# OZ440-SE100-CAR003_sheet11.net
KiCad netlist of a schematic drawn in Altium Designer
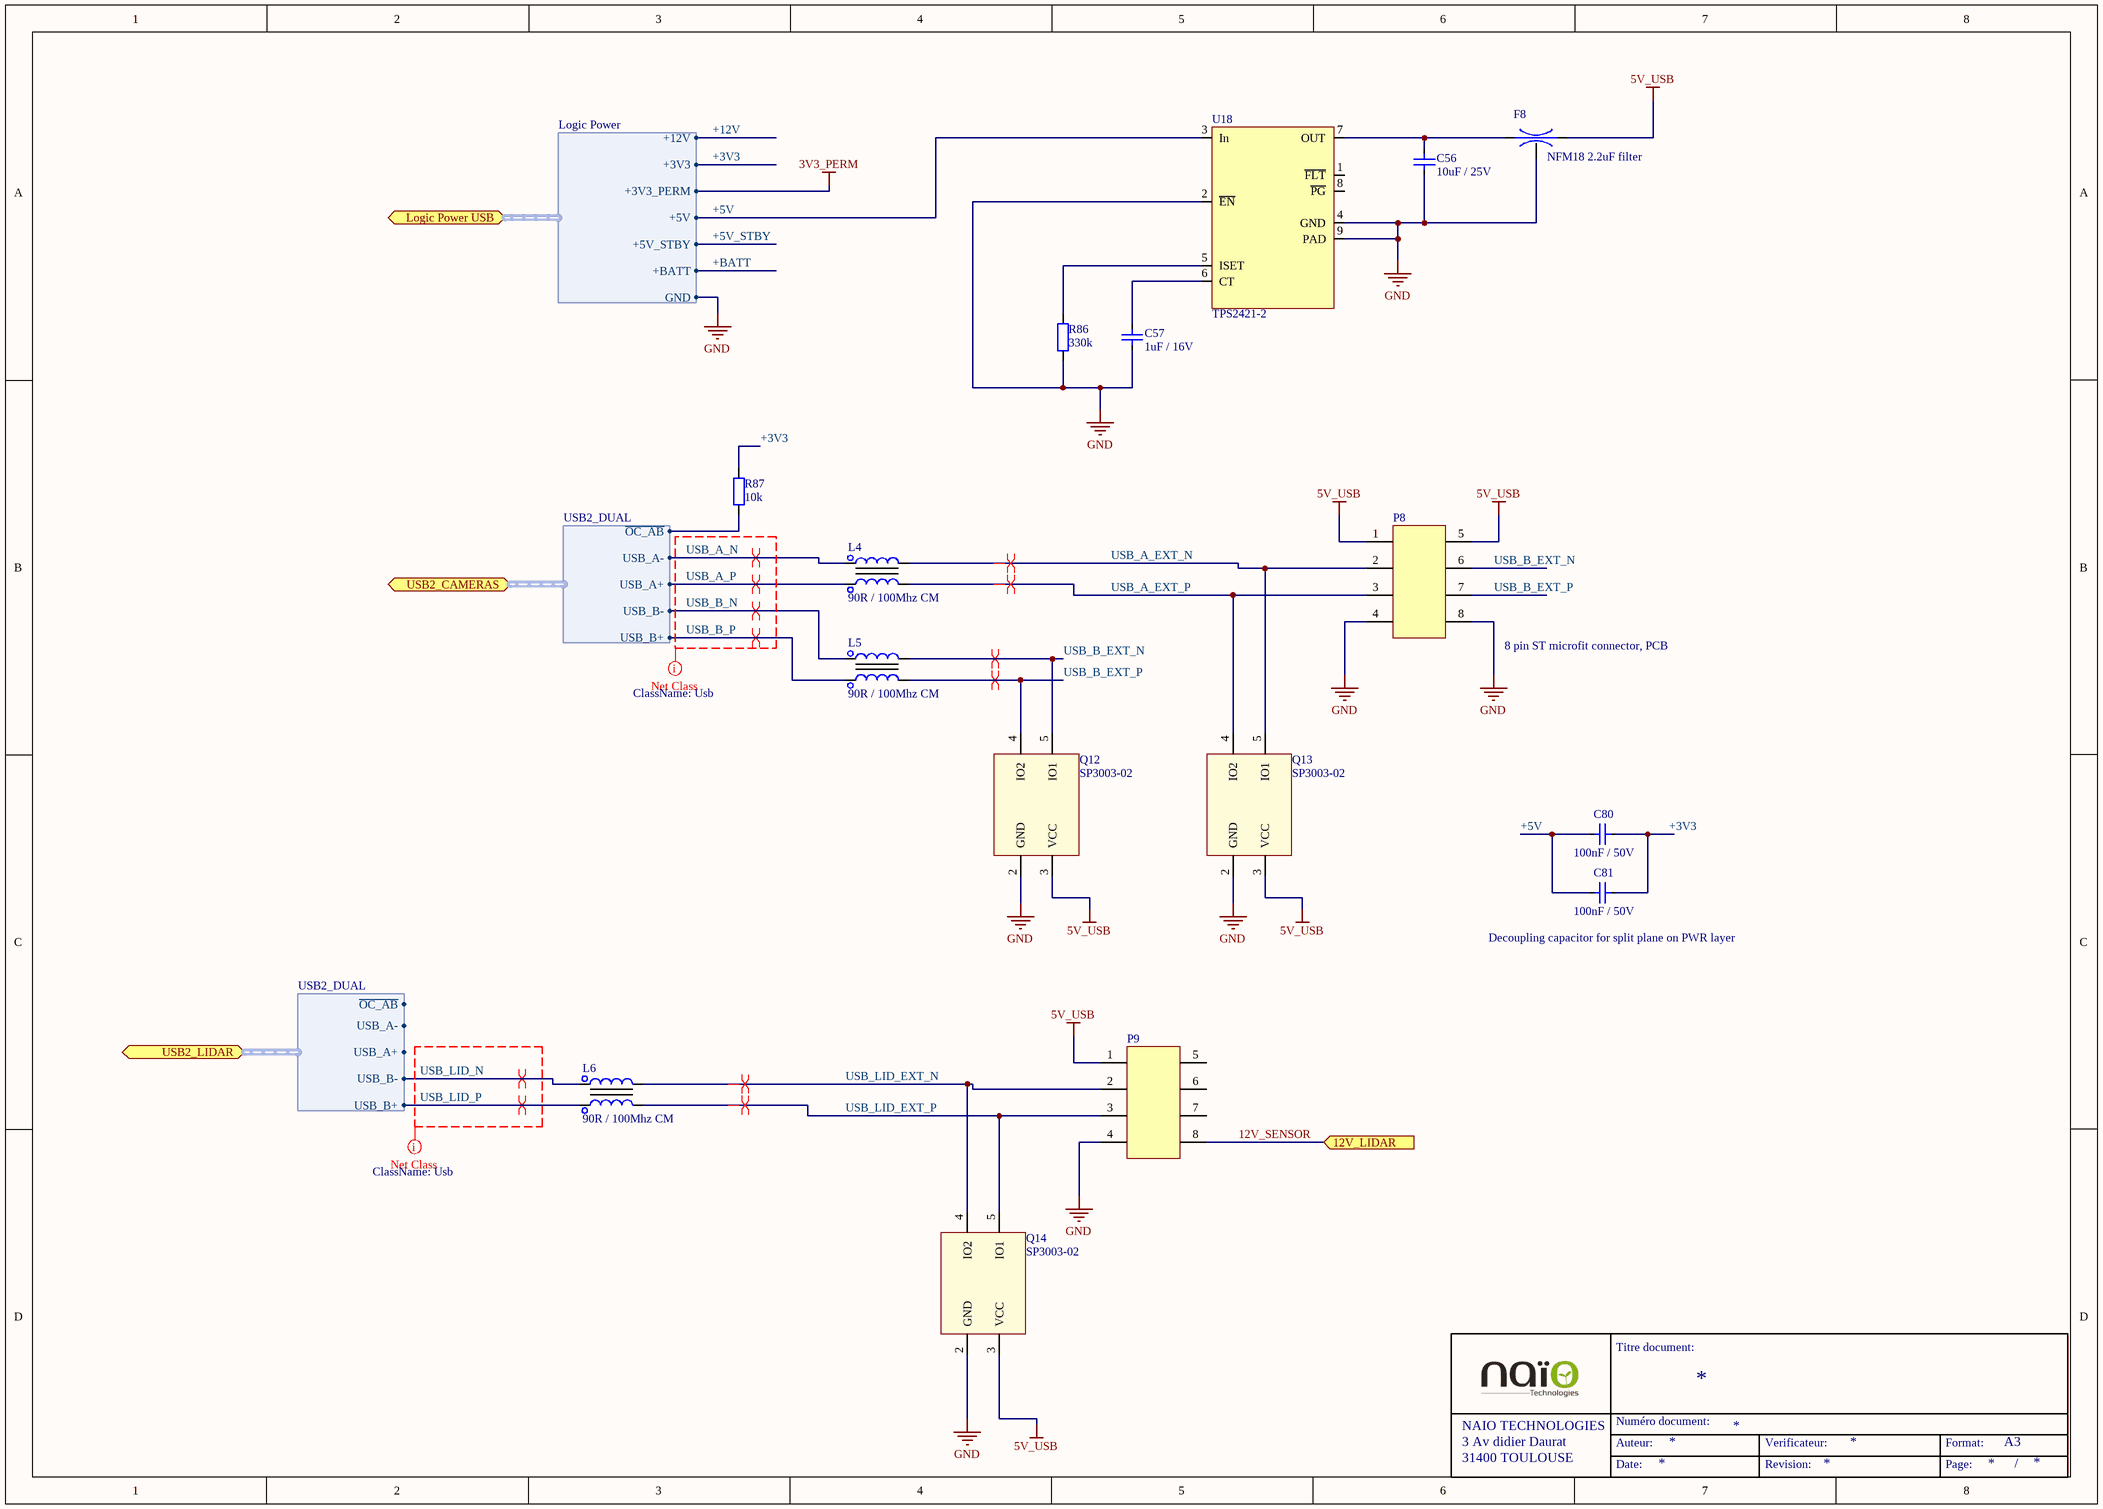
[diagram p0: OZ440-SE100-CAR003_sheet11.SchDoc]

(export (version "E")
  (design (tool "Eeschema 10.0.6"))
  (components
    (comp (ref "C56")
      (value "CAP-SMD")
      (footprint "C1206-STD")
      (description "1206 10uF / 25V X7R ceramic capacitor")
      (fields
        (field (name "DISPLAYED REFERENCE") "10uF / 25V")
        (field (name "TOLERANCE") "+/- 10%")
        (field (name "MANUFACTURER") "Kemet")
      )
      (libsource (lib "lib_NAIO") (part "CAP-SMD"))
    )
    (comp (ref "C57")
      (value "CAP-SMD")
      (footprint "C0805-STD")
      (description "0805 1uF / 16V X7R ceramic capacitor")
      (fields
        (field (name "DISPLAYED REFERENCE") "1uF / 16V")
        (field (name "TOLERANCE") "+/- 10%")
        (field (name "MANUFACTURER") "Kemet")
      )
      (libsource (lib "lib_NAIO") (part "CAP-SMD"))
    )
    (comp (ref "C80")
      (value "CAP-SMD")
      (footprint "C0805-STD")
      (description "0805 100nF / 50V  X7R ceramic capacitor")
      (fields
        (field (name "DISPLAYED REFERENCE") "100nF / 50V")
        (field (name "TOLERANCE") "+/- 10%")
        (field (name "MANUFACTURER") "vishay")
      )
      (libsource (lib "lib_NAIO") (part "CAP-SMD"))
    )
    (comp (ref "C81")
      (value "CAP-SMD")
      (footprint "C0805-STD")
      (description "0805 100nF / 50V  X7R ceramic capacitor")
      (fields
        (field (name "DISPLAYED REFERENCE") "100nF / 50V")
        (field (name "TOLERANCE") "+/- 10%")
        (field (name "MANUFACTURER") "vishay")
      )
      (libsource (lib "lib_NAIO") (part "CAP-SMD"))
    )
    (comp (ref "F8")
      (value "LC_FILTER-STD")
      (footprint "LC_0603-STD")
      (description "2A LC filter")
      (fields
        (field (name "DISPLAYED REFERENCE") "NFM18 2.2uF filter")
        (field (name "MANUFACTURER") "MURATA")
      )
      (libsource (lib "lib_NAIO") (part "LC_FILTER-STD"))
    )
    (comp (ref "L4")
      (value "IND-MC-SMD")
      (footprint "L-SPE-0805_MC_EXC34")
      (description "USB common mode inductor")
      (fields
        (field (name "DISPLAYED REFERENCE") "90R / 100Mhz CM")
        (field (name "MANUFACTURER") "PANASONIC")
      )
      (libsource (lib "lib_NAIO") (part "IND-MC-SMD"))
    )
    (comp (ref "L5")
      (value "IND-MC-SMD")
      (footprint "L-SPE-0805_MC_EXC34")
      (description "USB common mode inductor")
      (fields
        (field (name "DISPLAYED REFERENCE") "90R / 100Mhz CM")
        (field (name "MANUFACTURER") "PANASONIC")
      )
      (libsource (lib "lib_NAIO") (part "IND-MC-SMD"))
    )
    (comp (ref "L6")
      (value "IND-MC-SMD")
      (footprint "L-SPE-0805_MC_EXC34")
      (description "USB common mode inductor")
      (fields
        (field (name "DISPLAYED REFERENCE") "90R / 100Mhz CM")
        (field (name "MANUFACTURER") "PANASONIC")
      )
      (libsource (lib "lib_NAIO") (part "IND-MC-SMD"))
    )
    (comp (ref "P8")
      (value "CONN-SPE-8P_MOLEX_43045-0801")
      (footprint "CONN-SPE_MOLEX_43045-0812")
      (description "8 pin Microfit connector")
      (fields
        (field (name "DISPLAYED REFERENCE") "8 pin ST microfit connector, PCB")
        (field (name "MANUFACTURER") "Molex")
      )
      (libsource (lib "lib_NAIO") (part "CONN-SPE-8P_MOLEX_43045-0801"))
    )
    (comp (ref "P9")
      (value "CONN-SPE-8P_MOLEX_43045-0801")
      (footprint "CONN-SPE_MOLEX_43045-0812")
      (description "8 pin Microfit connector")
      (fields (field (name "MANUFACTURER") "Molex"))
      (libsource (lib "lib_NAIO") (part "CONN-SPE-8P_MOLEX_43045-0801"))
    )
    (comp (ref "Q12")
      (value "SP03003_02-SC70")
      (footprint "SC70-SPE-SP3003")
      (description "Low capacitance ESD TVS")
      (fields (field (name "DISPLAYED REFERENCE") "SP3003-02") (field (name "MANUFACTURER") "LITTLEFUSE"))
      (libsource (lib "lib_NAIO") (part "SP03003_02-SC70"))
    )
    (comp (ref "Q13")
      (value "SP03003_02-SC70")
      (footprint "SC70-SPE-SP3003")
      (description "Low capacitance ESD TVS")
      (fields (field (name "DISPLAYED REFERENCE") "SP3003-02") (field (name "MANUFACTURER") "LITTLEFUSE"))
      (libsource (lib "lib_NAIO") (part "SP03003_02-SC70"))
    )
    (comp (ref "Q14")
      (value "SP03003_02-SC70")
      (footprint "SC70-SPE-SP3003")
      (description "Low capacitance ESD TVS")
      (fields (field (name "DISPLAYED REFERENCE") "SP3003-02") (field (name "MANUFACTURER") "LITTLEFUSE"))
      (libsource (lib "lib_NAIO") (part "SP03003_02-SC70"))
    )
    (comp (ref "R86")
      (value "RES-SMD")
      (footprint "R0805-STD")
      (description "330k Ohm 0805 SMD resistor")
      (fields
        (field (name "DISPLAYED REFERENCE") "330k")
        (field (name "TOLERANCE") "1%")
        (field (name "MANUFACTURER") "Vishay")
      )
      (libsource (lib "") (part "RES-SMD_1"))
    )
    (comp (ref "R87")
      (value "RES-SMD")
      (footprint "R0805-STD")
      (description "10k Ohm 0805 SMD resistor")
      (fields
        (field (name "DISPLAYED REFERENCE") "10k")
        (field (name "TOLERANCE") "1 %")
        (field (name "MANUFACTURER") "Vishay")
      )
      (libsource (lib "lib_NAIO") (part "RES-SMD"))
    )
    (comp (ref "U18")
      (value "TPS2421-SO8")
      (footprint "SO8_THERMAL-STD")
      (description "20V-5A Hot plug controller with integrated FET, auto retry")
      (fields (field (name "DISPLAYED REFERENCE") "TPS2421-2") (field (name "MANUFACTURER") "TI"))
      (libsource (lib "lib_NAIO") (part "TPS2421-SO8"))
    )
  )
  (nets
    (net (code "4") (name "/+3V3") (class "Default")
      (node (ref "C80") (pin "1") (pinfunction "1_1") (pintype "passive"))
      (node (ref "C81") (pin "1") (pinfunction "1_1") (pintype "passive"))
      (node (ref "R87") (pin "1") (pinfunction "1_1") (pintype "passive"))
    )
    (net (code "5") (name "/+5V") (class "Default")
      (node (ref "C80") (pin "2") (pinfunction "2_2") (pintype "passive"))
      (node (ref "C81") (pin "2") (pinfunction "2_2") (pintype "passive"))
      (node (ref "U18") (pin "3") (pinfunction "In_3") (pintype "passive"))
    )
    (net (code "9") (name "/12V_SENSOR") (class "Default")
      (node (ref "P9") (pin "8") (pinfunction "8_8") (pintype "passive"))
    )
    (net (code "10") (name "/USB_A_EXT_N") (class "Default")
      (node (ref "L4") (pin "2") (pinfunction "2_2") (pintype "passive"))
      (node (ref "P8") (pin "2") (pinfunction "2_2") (pintype "passive"))
      (node (ref "Q13") (pin "5") (pinfunction "IO1_5") (pintype "passive"))
    )
    (net (code "11") (name "/USB_A_EXT_P") (class "Default")
      (node (ref "L4") (pin "3") (pinfunction "3_3") (pintype "passive"))
      (node (ref "P8") (pin "3") (pinfunction "3_3") (pintype "passive"))
      (node (ref "Q13") (pin "4") (pinfunction "IO2_4") (pintype "passive"))
    )
    (net (code "12") (name "/USB_A_N") (class "Default")
      (node (ref "L4") (pin "1") (pinfunction "1_1") (pintype "passive"))
    )
    (net (code "13") (name "/USB_A_P") (class "Default")
      (node (ref "L4") (pin "4") (pinfunction "4_4") (pintype "passive"))
    )
    (net (code "14") (name "/USB_B_EXT_N") (class "Default")
      (node (ref "L5") (pin "2") (pinfunction "2_2") (pintype "passive"))
      (node (ref "P8") (pin "6") (pinfunction "6_6") (pintype "passive"))
      (node (ref "Q12") (pin "5") (pinfunction "IO1_5") (pintype "passive"))
    )
    (net (code "15") (name "/USB_B_EXT_P") (class "Default")
      (node (ref "L5") (pin "3") (pinfunction "3_3") (pintype "passive"))
      (node (ref "P8") (pin "7") (pinfunction "7_7") (pintype "passive"))
      (node (ref "Q12") (pin "4") (pinfunction "IO2_4") (pintype "passive"))
    )
    (net (code "16") (name "/USB_B_N") (class "Default")
      (node (ref "L5") (pin "1") (pinfunction "1_1") (pintype "passive"))
    )
    (net (code "17") (name "/USB_B_P") (class "Default")
      (node (ref "L5") (pin "4") (pinfunction "4_4") (pintype "passive"))
    )
    (net (code "18") (name "/USB_LID_EXT_N") (class "Default")
      (node (ref "L6") (pin "2") (pinfunction "2_2") (pintype "passive"))
      (node (ref "P9") (pin "2") (pinfunction "2_2") (pintype "passive"))
      (node (ref "Q14") (pin "4") (pinfunction "IO2_4") (pintype "passive"))
    )
    (net (code "19") (name "/USB_LID_EXT_P") (class "Default")
      (node (ref "L6") (pin "3") (pinfunction "3_3") (pintype "passive"))
      (node (ref "P9") (pin "3") (pinfunction "3_3") (pintype "passive"))
      (node (ref "Q14") (pin "5") (pinfunction "IO1_5") (pintype "passive"))
    )
    (net (code "20") (name "/USB_LID_N") (class "Default")
      (node (ref "L6") (pin "1") (pinfunction "1_1") (pintype "passive"))
    )
    (net (code "21") (name "/USB_LID_P") (class "Default")
      (node (ref "L6") (pin "4") (pinfunction "4_4") (pintype "passive"))
    )
    (net (code "25") (name "5V_USB") (class "Default")
      (node (ref "F8") (pin "2") (pinfunction "B_2") (pintype "passive"))
      (node (ref "P8") (pin "1") (pinfunction "1_1") (pintype "passive"))
      (node (ref "P8") (pin "5") (pinfunction "9_5") (pintype "passive"))
      (node (ref "P9") (pin "1") (pinfunction "1_1") (pintype "passive"))
      (node (ref "Q12") (pin "3") (pinfunction "VCC_3") (pintype "passive"))
      (node (ref "Q13") (pin "3") (pinfunction "VCC_3") (pintype "passive"))
      (node (ref "Q14") (pin "3") (pinfunction "VCC_3") (pintype "passive"))
    )
    (net (code "26") (name "GND") (class "Default")
      (node (ref "C56") (pin "1") (pinfunction "1_1") (pintype "passive"))
      (node (ref "C57") (pin "1") (pinfunction "1_1") (pintype "passive"))
      (node (ref "F8") (pin "3") (pinfunction "G_3") (pintype "passive"))
      (node (ref "P8") (pin "4") (pinfunction "7_4") (pintype "passive"))
      (node (ref "P8") (pin "8") (pinfunction "8_8") (pintype "passive"))
      (node (ref "P9") (pin "4") (pinfunction "7_4") (pintype "passive"))
      (node (ref "Q12") (pin "2") (pinfunction "GND_2") (pintype "passive"))
      (node (ref "Q13") (pin "2") (pinfunction "GND_2") (pintype "passive"))
      (node (ref "Q14") (pin "2") (pinfunction "GND_2") (pintype "passive"))
      (node (ref "R86") (pin "1") (pinfunction "1_1") (pintype "passive"))
      (node (ref "U18") (pin "2") (pinfunction "EN_2") (pintype "passive"))
      (node (ref "U18") (pin "4") (pinfunction "GND_4") (pintype "passive"))
      (node (ref "U18") (pin "9") (pinfunction "PAD_9") (pintype "passive"))
    )
    (net (code "27") (name "Net-(F8-A)") (class "Default")
      (node (ref "C56") (pin "2") (pinfunction "2_2") (pintype "passive"))
      (node (ref "F8") (pin "1") (pinfunction "A_1") (pintype "passive"))
      (node (ref "U18") (pin "7") (pinfunction "OUT_7") (pintype "passive"))
    )
    (net (code "28") (name "Net-(U18-CT)") (class "Default")
      (node (ref "C57") (pin "2") (pinfunction "2_2") (pintype "passive"))
      (node (ref "U18") (pin "6") (pinfunction "CT_6") (pintype "passive"))
    )
    (net (code "29") (name "Net-(U18-ISET)") (class "Default")
      (node (ref "R86") (pin "2") (pinfunction "2_2") (pintype "passive"))
      (node (ref "U18") (pin "5") (pinfunction "ISET_5") (pintype "passive"))
    )
    (net (code "30") (name "unconnected-(P9-9-Pad5)") (class "Default")
      (node (ref "P9") (pin "5") (pinfunction "9_5") (pintype "passive"))
    )
    (net (code "31") (name "unconnected-(P9-Pad6)") (class "Default")
      (node (ref "P9") (pin "6") (pinfunction "6_6") (pintype "passive"))
    )
    (net (code "32") (name "unconnected-(P9-Pad7)") (class "Default")
      (node (ref "P9") (pin "7") (pinfunction "7_7") (pintype "passive"))
    )
    (net (code "33") (name "unconnected-(R87-Pad2)") (class "Default")
      (node (ref "R87") (pin "2") (pinfunction "2_2") (pintype "passive"))
    )
    (net (code "34") (name "unconnected-(U18-FLT-Pad1)") (class "Default")
      (node (ref "U18") (pin "1") (pinfunction "FLT_1") (pintype "passive"))
    )
    (net (code "35") (name "unconnected-(U18-PG-Pad8)") (class "Default")
      (node (ref "U18") (pin "8") (pinfunction "PG_8") (pintype "passive"))
    )
  )
)
